# CH32L103F7P6-R0.net
KiCad netlist of a schematic drawn in Altium Designer
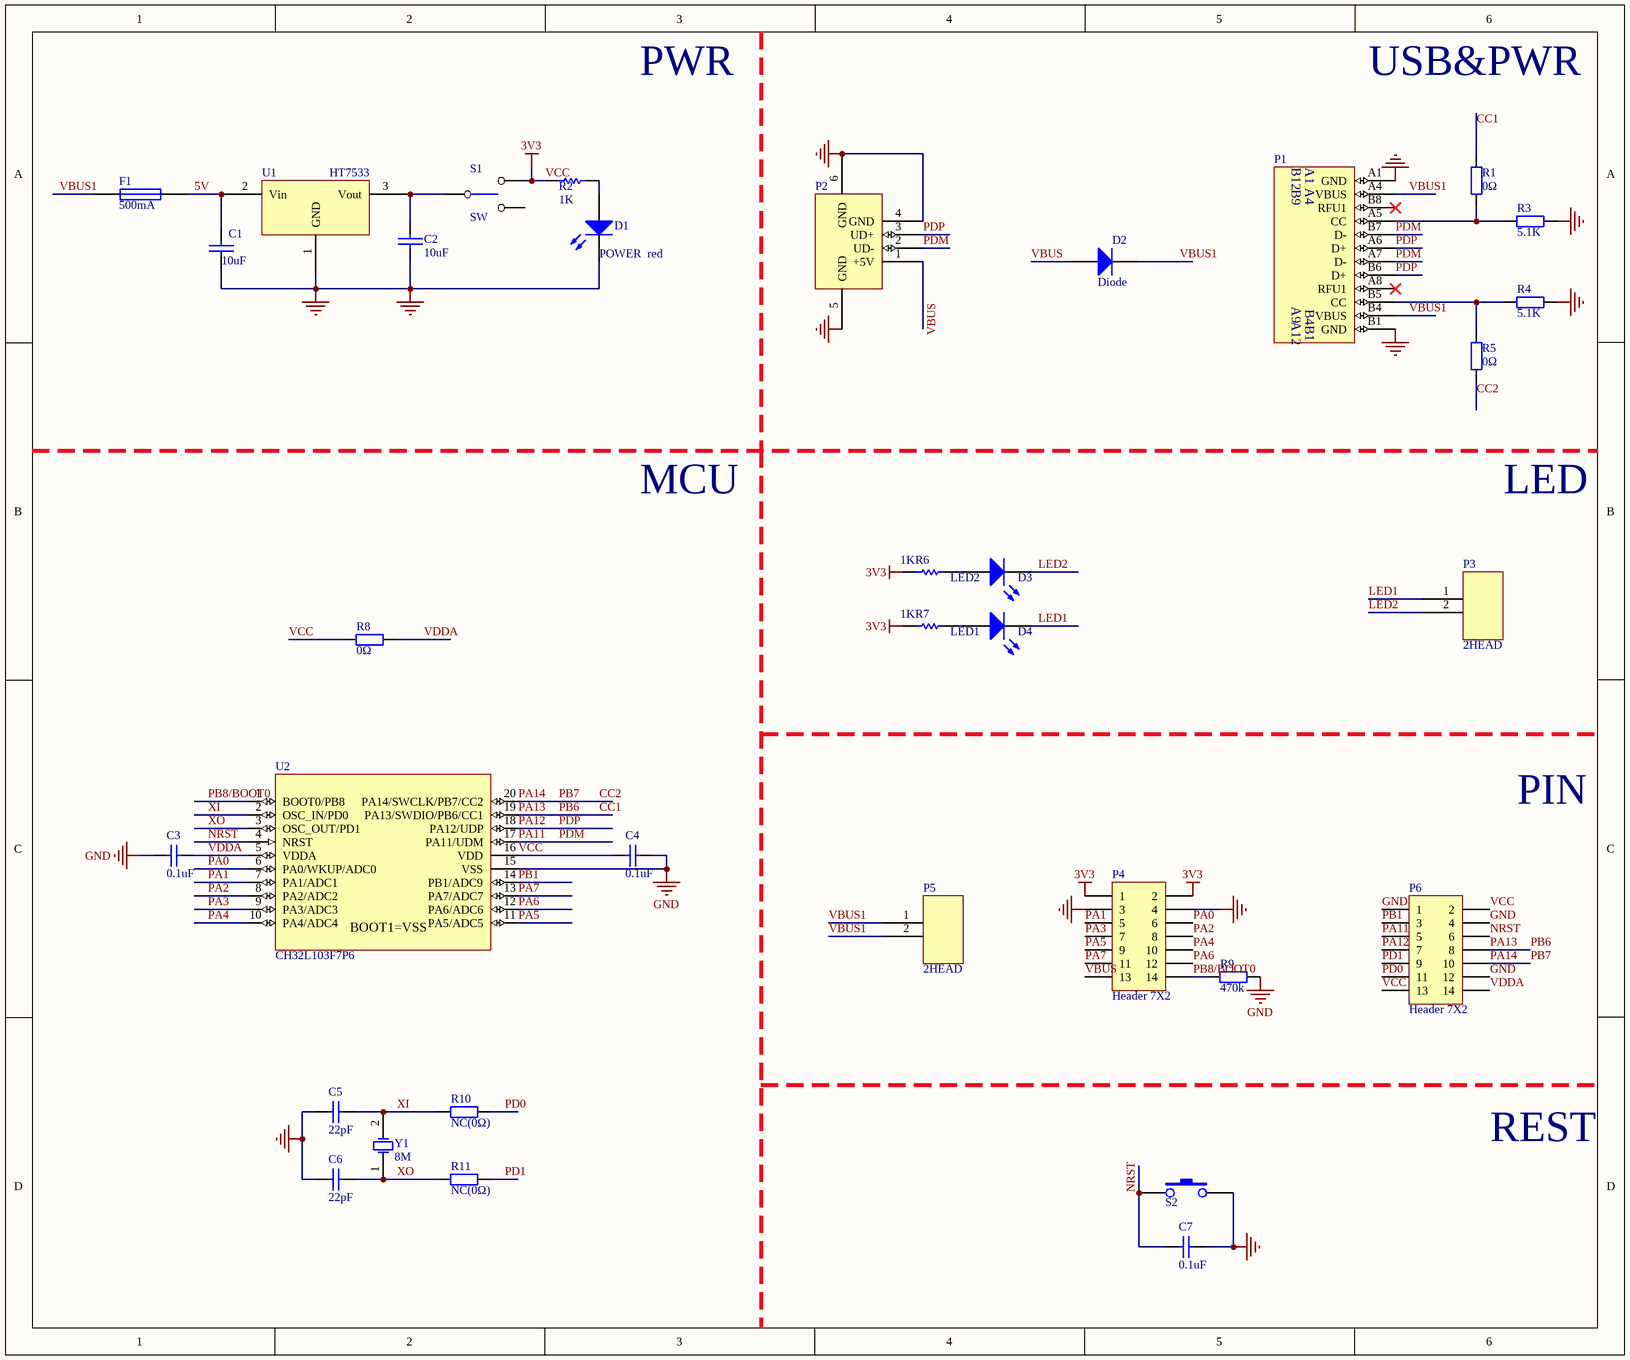
[diagram p0: CH32L103F7P6-R0.SchDoc]

(export (version "E")
  (design (tool "Eeschema 10.0.6"))
  (components
    (comp (ref "C1")
      (value "10uF")
      (footprint "0603_C")
      (description "Capacitor")
      (libsource (lib "*") (part "CAP"))
    )
    (comp (ref "C2")
      (value "10uF")
      (footprint "0603_C")
      (description "Capacitor")
      (libsource (lib "*") (part "CAP"))
    )
    (comp (ref "C3")
      (value "0.1uF")
      (footprint "0603_C")
      (description "Capacitor")
      (fields (field (name "PUBLISHER") "Altium Limited"))
      (libsource (lib "*") (part "Cap"))
    )
    (comp (ref "C4")
      (value "0.1uF")
      (footprint "0603_C")
      (description "Capacitor")
      (fields (field (name "PUBLISHER") "Altium Limited"))
      (libsource (lib "*") (part "Cap"))
    )
    (comp (ref "C5")
      (value "22pF")
      (footprint "0603_C")
      (description "Capacitor")
      (fields (field (name "PUBLISHER") "Altium Limited"))
      (libsource (lib "*") (part "Cap"))
    )
    (comp (ref "C6")
      (value "22pF")
      (footprint "0603_C")
      (description "Capacitor")
      (fields (field (name "PUBLISHER") "Altium Limited"))
      (libsource (lib "*") (part "Cap"))
    )
    (comp (ref "C7")
      (value "0.1uF")
      (footprint "0603_C")
      (description "Capacitor")
      (fields (field (name "PUBLISHER") "Altium Limited"))
      (libsource (lib "*") (part "Cap"))
    )
    (comp (ref "D1")
      (value "POWER  red")
      (footprint "0603+")
      (description "Typical INFRARED GaAs LED")
      (fields (field (name "PUBLISHER") "Altium Limited"))
      (libsource (lib "*") (part "LED0"))
    )
    (comp (ref "D2")
      (value "Diode")
      (footprint "SOD-123")
      (description "Default Diode")
      (fields (field (name "PUBLISHER") "Altium Limited"))
      (libsource (lib "Miscellaneous Devices") (part "Diode"))
    )
    (comp (ref "D3")
      (value "LED2")
      (footprint "0603+")
      (description "Typical INFRARED GaAs LED")
      (fields (field (name "PUBLISHER") "Altium Limited"))
      (libsource (lib "*") (part "LED0"))
    )
    (comp (ref "D4")
      (value "LED1")
      (footprint "0603+")
      (description "Typical INFRARED GaAs LED")
      (fields (field (name "PUBLISHER") "Altium Limited"))
      (libsource (lib "*") (part "LED0"))
    )
    (comp (ref "F1")
      (value "500mA")
      (footprint "0603")
      (description "Fuse")
      (libsource (lib "*") (part "FUSE1"))
    )
    (comp (ref "P1")
      (value "TYPE-C")
      (footprint "TYPE-C-Receptacle-2.0")
      (libsource (lib "*") (part "TYPE-C1"))
    )
    (comp (ref "P2")
      (value "USB_A")
      (footprint "USBAF")
      (description "USB Port")
      (libsource (lib "*") (part "USB"))
    )
    (comp (ref "P3") (value "2HEAD") (footprint "SIP2-2.54mm") (libsource (lib "*") (part "2HEAD")))
    (comp (ref "P4")
      (value "Header 7X2")
      (footprint "IDC14-2.54mm")
      (description "Header, 7-Pin, Dual row")
      (fields (field (name "PUBLISHER") "Altium Limited"))
      (libsource (lib "Miscellaneous Connectors") (part "Header 7X2"))
    )
    (comp (ref "P5") (value "2HEAD") (footprint "SIP2-2.54mm") (libsource (lib "*") (part "2HEAD")))
    (comp (ref "P6")
      (value "Header 7X2")
      (footprint "IDC14-2.54mm")
      (description "Header, 7-Pin, Dual row")
      (fields (field (name "PUBLISHER") "Altium Limited"))
      (libsource (lib "Miscellaneous Connectors") (part "Header 7X2"))
    )
    (comp (ref "R1")
      (value "0Ω")
      (footprint "0603")
      (description "Resistor")
      (libsource (lib "") (part "Res2_1"))
    )
    (comp (ref "R2")
      (value "1K")
      (footprint "0603")
      (description "Semiconductor Resistor")
      (libsource (lib "*") (part "Res Semi"))
    )
    (comp (ref "R3")
      (value "5.1K")
      (footprint "0603")
      (description "Resistor")
      (libsource (lib "Miscellaneous Devices") (part "Res2"))
    )
    (comp (ref "R4")
      (value "5.1K")
      (footprint "0603")
      (description "Resistor")
      (libsource (lib "Miscellaneous Devices") (part "Res2"))
    )
    (comp (ref "R5")
      (value "0Ω")
      (footprint "0603")
      (description "Resistor")
      (libsource (lib "") (part "Res2_1"))
    )
    (comp (ref "R6")
      (value "1K")
      (footprint "0603")
      (description "Semiconductor Resistor")
      (libsource (lib "*") (part "Res Semi"))
    )
    (comp (ref "R7")
      (value "1K")
      (footprint "0603")
      (description "Semiconductor Resistor")
      (libsource (lib "*") (part "Res Semi"))
    )
    (comp (ref "R8")
      (value "0Ω")
      (footprint "0603")
      (description "Resistor")
      (libsource (lib "Miscellaneous Devices") (part "Res2"))
    )
    (comp (ref "R9")
      (value "470k")
      (footprint "0603")
      (description "Resistor")
      (libsource (lib "Miscellaneous Devices") (part "Res2"))
    )
    (comp (ref "R10")
      (value "NC(0Ω)")
      (footprint "0603")
      (description "Resistor")
      (libsource (lib "") (part "Res2_2"))
    )
    (comp (ref "R11")
      (value "NC(0Ω)")
      (footprint "0603")
      (description "Resistor")
      (libsource (lib "") (part "Res2_2"))
    )
    (comp (ref "S1") (value "SW") (footprint "SW1") (libsource (lib "*") (part "SW")))
    (comp (ref "S2") (value "KEY") (footprint "贴片按键") (libsource (lib "*") (part "KEY")))
    (comp (ref "U1")
      (value "HT7533")
      (footprint "SOT-89")
      (libsource (lib "wch_sch_others") (part "1117-3.3V"))
    )
    (comp (ref "U2")
      (value "CH32L103F7P6")
      (footprint "TSSOP20")
      (description "RISC-V LMD-MCU, 96MHz, USB, Type-C/PD, CAN, OPA, lower power")
      (libsource (lib "CHXXX") (part "CH32L103F7P6"))
    )
    (comp (ref "Y1")
      (value "8M")
      (footprint "XT_AT49")
      (description "Crystal Oscillator")
      (fields (field (name "PUBLISHER") "Altium Limited"))
      (libsource (lib "*") (part "XTAL"))
    )
  )
  (nets
    (net (code "1") (name "/5V") (class "Default")
      (node (ref "C1") (pin "1") (pinfunction "1_1") (pintype "passive"))
      (node (ref "F1") (pin "2") (pinfunction "2_2") (pintype "passive"))
      (node (ref "U1") (pin "2") (pinfunction "Vin_2") (pintype "passive"))
    )
    (net (code "3") (name "/CC1") (class "Default")
      (node (ref "P6") (pin "8") (pinfunction "8_8") (pintype "passive"))
      (node (ref "R1") (pin "2") (pinfunction "2_2") (pintype "passive"))
      (node (ref "U2") (pin "19") (pinfunction "PA13/SWDIO/PB6/CC1_19") (pintype "bidirectional"))
    )
    (net (code "4") (name "/CC2") (class "Default")
      (node (ref "P6") (pin "10") (pinfunction "10_10") (pintype "passive"))
      (node (ref "R5") (pin "1") (pinfunction "1_1") (pintype "passive"))
      (node (ref "U2") (pin "20") (pinfunction "PA14/SWCLK/PB7/CC2_20") (pintype "bidirectional"))
    )
    (net (code "5") (name "/LED1") (class "Default")
      (node (ref "D4") (pin "2") (pinfunction "K_2") (pintype "passive"))
      (node (ref "P3") (pin "1") (pintype "passive"))
    )
    (net (code "6") (name "/LED2") (class "Default")
      (node (ref "D3") (pin "2") (pinfunction "K_2") (pintype "passive"))
      (node (ref "P3") (pin "2") (pintype "passive"))
    )
    (net (code "7") (name "/NRST") (class "Default")
      (node (ref "C7") (pin "2") (pinfunction "2_2") (pintype "passive"))
      (node (ref "P6") (pin "6") (pinfunction "6_6") (pintype "passive"))
      (node (ref "S2") (pin "1") (pinfunction "1_1") (pintype "passive"))
      (node (ref "U2") (pin "4") (pinfunction "NRST_4") (pintype "input"))
    )
    (net (code "8") (name "/PA0") (class "Default")
      (node (ref "P4") (pin "6") (pinfunction "6_6") (pintype "passive"))
      (node (ref "U2") (pin "6") (pinfunction "PA0/WKUP/ADC0_6") (pintype "bidirectional"))
    )
    (net (code "9") (name "/PA1") (class "Default")
      (node (ref "P4") (pin "5") (pinfunction "5_5") (pintype "passive"))
      (node (ref "U2") (pin "7") (pinfunction "PA1/ADC1_7") (pintype "bidirectional"))
    )
    (net (code "10") (name "/PA2") (class "Default")
      (node (ref "P4") (pin "8") (pinfunction "8_8") (pintype "passive"))
      (node (ref "U2") (pin "8") (pinfunction "PA2/ADC2_8") (pintype "bidirectional"))
    )
    (net (code "11") (name "/PA3") (class "Default")
      (node (ref "P4") (pin "7") (pinfunction "7_7") (pintype "passive"))
      (node (ref "U2") (pin "9") (pinfunction "PA3/ADC3_9") (pintype "bidirectional"))
    )
    (net (code "12") (name "/PA4") (class "Default")
      (node (ref "P4") (pin "10") (pinfunction "10_10") (pintype "passive"))
      (node (ref "U2") (pin "10") (pinfunction "PA4/ADC4_10") (pintype "bidirectional"))
    )
    (net (code "13") (name "/PA5") (class "Default")
      (node (ref "P4") (pin "9") (pinfunction "9_9") (pintype "passive"))
      (node (ref "U2") (pin "11") (pinfunction "PA5/ADC5_11") (pintype "bidirectional"))
    )
    (net (code "14") (name "/PA6") (class "Default")
      (node (ref "P4") (pin "12") (pinfunction "12_12") (pintype "passive"))
      (node (ref "U2") (pin "12") (pinfunction "PA6/ADC6_12") (pintype "bidirectional"))
    )
    (net (code "15") (name "/PA7") (class "Default")
      (node (ref "P4") (pin "11") (pinfunction "11_11") (pintype "passive"))
      (node (ref "U2") (pin "13") (pinfunction "PA7/ADC7_13") (pintype "bidirectional"))
    )
    (net (code "16") (name "/PA11") (class "Default")
      (node (ref "P1") (pin "A7") (pinfunction "D-_A7") (pintype "bidirectional"))
      (node (ref "P1") (pin "B7") (pinfunction "D-_B7") (pintype "bidirectional"))
      (node (ref "P2") (pin "2") (pinfunction "UD-_2") (pintype "bidirectional"))
      (node (ref "P6") (pin "5") (pinfunction "5_5") (pintype "passive"))
      (node (ref "U2") (pin "17") (pinfunction "PA11/UDM_17") (pintype "bidirectional"))
    )
    (net (code "17") (name "/PA12") (class "Default")
      (node (ref "P1") (pin "A6") (pinfunction "D+_A6") (pintype "bidirectional"))
      (node (ref "P1") (pin "B6") (pinfunction "D+_B6") (pintype "bidirectional"))
      (node (ref "P2") (pin "3") (pinfunction "UD+_3") (pintype "bidirectional"))
      (node (ref "P6") (pin "7") (pinfunction "7_7") (pintype "passive"))
      (node (ref "U2") (pin "18") (pinfunction "PA12/UDP_18") (pintype "bidirectional"))
    )
    (net (code "18") (name "/PB1") (class "Default")
      (node (ref "P6") (pin "3") (pinfunction "3_3") (pintype "passive"))
      (node (ref "U2") (pin "14") (pinfunction "PB1/ADC9_14") (pintype "bidirectional"))
    )
    (net (code "19") (name "/PB8{slash}BOOT0") (class "Default")
      (node (ref "P4") (pin "14") (pinfunction "14_14") (pintype "passive"))
      (node (ref "R9") (pin "1") (pinfunction "1_1") (pintype "passive"))
      (node (ref "U2") (pin "1") (pinfunction "BOOT0/PB8_1") (pintype "bidirectional"))
    )
    (net (code "20") (name "/PD0") (class "Default")
      (node (ref "P6") (pin "11") (pinfunction "11_11") (pintype "passive"))
      (node (ref "R10") (pin "1") (pinfunction "1_1") (pintype "passive"))
    )
    (net (code "21") (name "/PD1") (class "Default")
      (node (ref "P6") (pin "9") (pinfunction "9_9") (pintype "passive"))
      (node (ref "R11") (pin "1") (pinfunction "1_1") (pintype "passive"))
    )
    (net (code "22") (name "/VBUS") (class "Default")
      (node (ref "D2") (pin "1") (pinfunction "A_1") (pintype "passive"))
      (node (ref "P2") (pin "1") (pinfunction "+5V_1") (pintype "power_in"))
      (node (ref "P4") (pin "13") (pinfunction "13_13") (pintype "passive"))
    )
    (net (code "23") (name "/VBUS1") (class "Default")
      (node (ref "D2") (pin "2") (pinfunction "K_2") (pintype "passive"))
      (node (ref "F1") (pin "1") (pinfunction "1_1") (pintype "passive"))
      (node (ref "P1") (pin "A4") (pinfunction "VBUS_A4") (pintype "bidirectional"))
      (node (ref "P1") (pin "B4") (pinfunction "VBUS_B4") (pintype "bidirectional"))
      (node (ref "P5") (pin "1") (pintype "passive"))
      (node (ref "P5") (pin "2") (pintype "passive"))
    )
    (net (code "24") (name "/VDDA") (class "Default")
      (node (ref "C3") (pin "1") (pinfunction "1_1") (pintype "passive"))
      (node (ref "P6") (pin "14") (pinfunction "14_14") (pintype "passive"))
      (node (ref "R8") (pin "2") (pinfunction "2_2") (pintype "passive"))
      (node (ref "U2") (pin "5") (pinfunction "VDDA_5") (pintype "bidirectional"))
    )
    (net (code "25") (name "/XI") (class "Default")
      (node (ref "C5") (pin "2") (pinfunction "2_2") (pintype "passive"))
      (node (ref "R10") (pin "2") (pinfunction "2_2") (pintype "passive"))
      (node (ref "U2") (pin "2") (pinfunction "OSC_IN/PD0_2") (pintype "bidirectional"))
      (node (ref "Y1") (pin "2") (pinfunction "OSC2_2") (pintype "passive"))
    )
    (net (code "26") (name "/XO") (class "Default")
      (node (ref "C6") (pin "2") (pinfunction "2_2") (pintype "passive"))
      (node (ref "R11") (pin "2") (pinfunction "2_2") (pintype "passive"))
      (node (ref "U2") (pin "3") (pinfunction "OSC_OUT/PD1_3") (pintype "bidirectional"))
      (node (ref "Y1") (pin "1") (pinfunction "OSC1_1") (pintype "passive"))
    )
    (net (code "27") (name "3V3") (class "Default")
      (node (ref "C4") (pin "1") (pinfunction "1_1") (pintype "passive"))
      (node (ref "P4") (pin "1") (pinfunction "1_1") (pintype "passive"))
      (node (ref "P4") (pin "2") (pinfunction "2_2") (pintype "passive"))
      (node (ref "P6") (pin "13") (pinfunction "13_13") (pintype "passive"))
      (node (ref "P6") (pin "2") (pinfunction "2_2") (pintype "passive"))
      (node (ref "R2") (pin "2") (pinfunction "2_2") (pintype "passive"))
      (node (ref "R6") (pin "1") (pinfunction "1_1") (pintype "passive"))
      (node (ref "R7") (pin "1") (pinfunction "1_1") (pintype "passive"))
      (node (ref "R8") (pin "1") (pinfunction "1_1") (pintype "passive"))
      (node (ref "S1") (pin "3") (pinfunction "3_3") (pintype "passive"))
      (node (ref "U2") (pin "16") (pinfunction "VDD_16") (pintype "power_in"))
    )
    (net (code "28") (name "GND") (class "Default")
      (node (ref "C1") (pin "2") (pinfunction "2_2") (pintype "passive"))
      (node (ref "C2") (pin "2") (pinfunction "2_2") (pintype "passive"))
      (node (ref "C3") (pin "2") (pinfunction "2_2") (pintype "passive"))
      (node (ref "C4") (pin "2") (pinfunction "2_2") (pintype "passive"))
      (node (ref "C5") (pin "1") (pinfunction "1_1") (pintype "passive"))
      (node (ref "C6") (pin "1") (pinfunction "1_1") (pintype "passive"))
      (node (ref "C7") (pin "1") (pinfunction "1_1") (pintype "passive"))
      (node (ref "D1") (pin "2") (pinfunction "K_2") (pintype "passive"))
      (node (ref "P1") (pin "A1") (pinfunction "GND_A1") (pintype "bidirectional"))
      (node (ref "P1") (pin "B1") (pinfunction "GND_B1") (pintype "bidirectional"))
      (node (ref "P2") (pin "4") (pinfunction "GND_4") (pintype "power_in"))
      (node (ref "P2") (pin "5") (pinfunction "GND_5") (pintype "power_in"))
      (node (ref "P2") (pin "6") (pinfunction "GND_6") (pintype "power_in"))
      (node (ref "P4") (pin "3") (pinfunction "3_3") (pintype "passive"))
      (node (ref "P4") (pin "4") (pinfunction "4_4") (pintype "passive"))
      (node (ref "P6") (pin "1") (pinfunction "1_1") (pintype "passive"))
      (node (ref "P6") (pin "12") (pinfunction "12_12") (pintype "passive"))
      (node (ref "P6") (pin "4") (pinfunction "4_4") (pintype "passive"))
      (node (ref "R3") (pin "2") (pinfunction "2_2") (pintype "passive"))
      (node (ref "R4") (pin "2") (pinfunction "2_2") (pintype "passive"))
      (node (ref "R9") (pin "2") (pinfunction "2_2") (pintype "passive"))
      (node (ref "S2") (pin "3") (pinfunction "3_3") (pintype "passive"))
      (node (ref "U1") (pin "1") (pinfunction "GND_1") (pintype "passive"))
      (node (ref "U2") (pin "15") (pinfunction "VSS_15") (pintype "power_in"))
    )
    (net (code "29") (name "Net-(D1-A)") (class "Default")
      (node (ref "D1") (pin "1") (pinfunction "A_1") (pintype "passive"))
      (node (ref "R2") (pin "1") (pinfunction "1_1") (pintype "passive"))
    )
    (net (code "30") (name "Net-(D3-A)") (class "Default")
      (node (ref "D3") (pin "1") (pinfunction "A_1") (pintype "passive"))
      (node (ref "R6") (pin "2") (pinfunction "2_2") (pintype "passive"))
    )
    (net (code "31") (name "Net-(D4-A)") (class "Default")
      (node (ref "D4") (pin "1") (pinfunction "A_1") (pintype "passive"))
      (node (ref "R7") (pin "2") (pinfunction "2_2") (pintype "passive"))
    )
    (net (code "32") (name "Net-(P1-CC-PadA5)") (class "Default")
      (node (ref "P1") (pin "A5") (pinfunction "CC_A5") (pintype "bidirectional"))
      (node (ref "R1") (pin "1") (pinfunction "1_1") (pintype "passive"))
      (node (ref "R3") (pin "1") (pinfunction "1_1") (pintype "passive"))
    )
    (net (code "33") (name "Net-(P1-CC-PadB5)") (class "Default")
      (node (ref "P1") (pin "B5") (pinfunction "CC_B5") (pintype "bidirectional"))
      (node (ref "R4") (pin "1") (pinfunction "1_1") (pintype "passive"))
      (node (ref "R5") (pin "2") (pinfunction "2_2") (pintype "passive"))
    )
    (net (code "34") (name "Net-(U1-Vout)") (class "Default")
      (node (ref "C2") (pin "1") (pinfunction "1_1") (pintype "passive"))
      (node (ref "S1") (pin "1") (pinfunction "1_1") (pintype "passive"))
      (node (ref "U1") (pin "3") (pinfunction "Vout_3") (pintype "passive"))
    )
    (net (code "35") (name "unconnected-(P1-RFU1-PadA8)") (class "Default")
      (node (ref "P1") (pin "A8") (pinfunction "RFU1_A8") (pintype "bidirectional+no_connect"))
    )
    (net (code "36") (name "unconnected-(P1-RFU1-PadB8)") (class "Default")
      (node (ref "P1") (pin "B8") (pinfunction "RFU1_B8") (pintype "bidirectional+no_connect"))
    )
    (net (code "37") (name "unconnected-(S1-Pad2)") (class "Default")
      (node (ref "S1") (pin "2") (pinfunction "2_2") (pintype "passive"))
    )
  )
)
